# CH32F_V208G-R0.net
KiCad netlist of a schematic drawn in Altium Designer
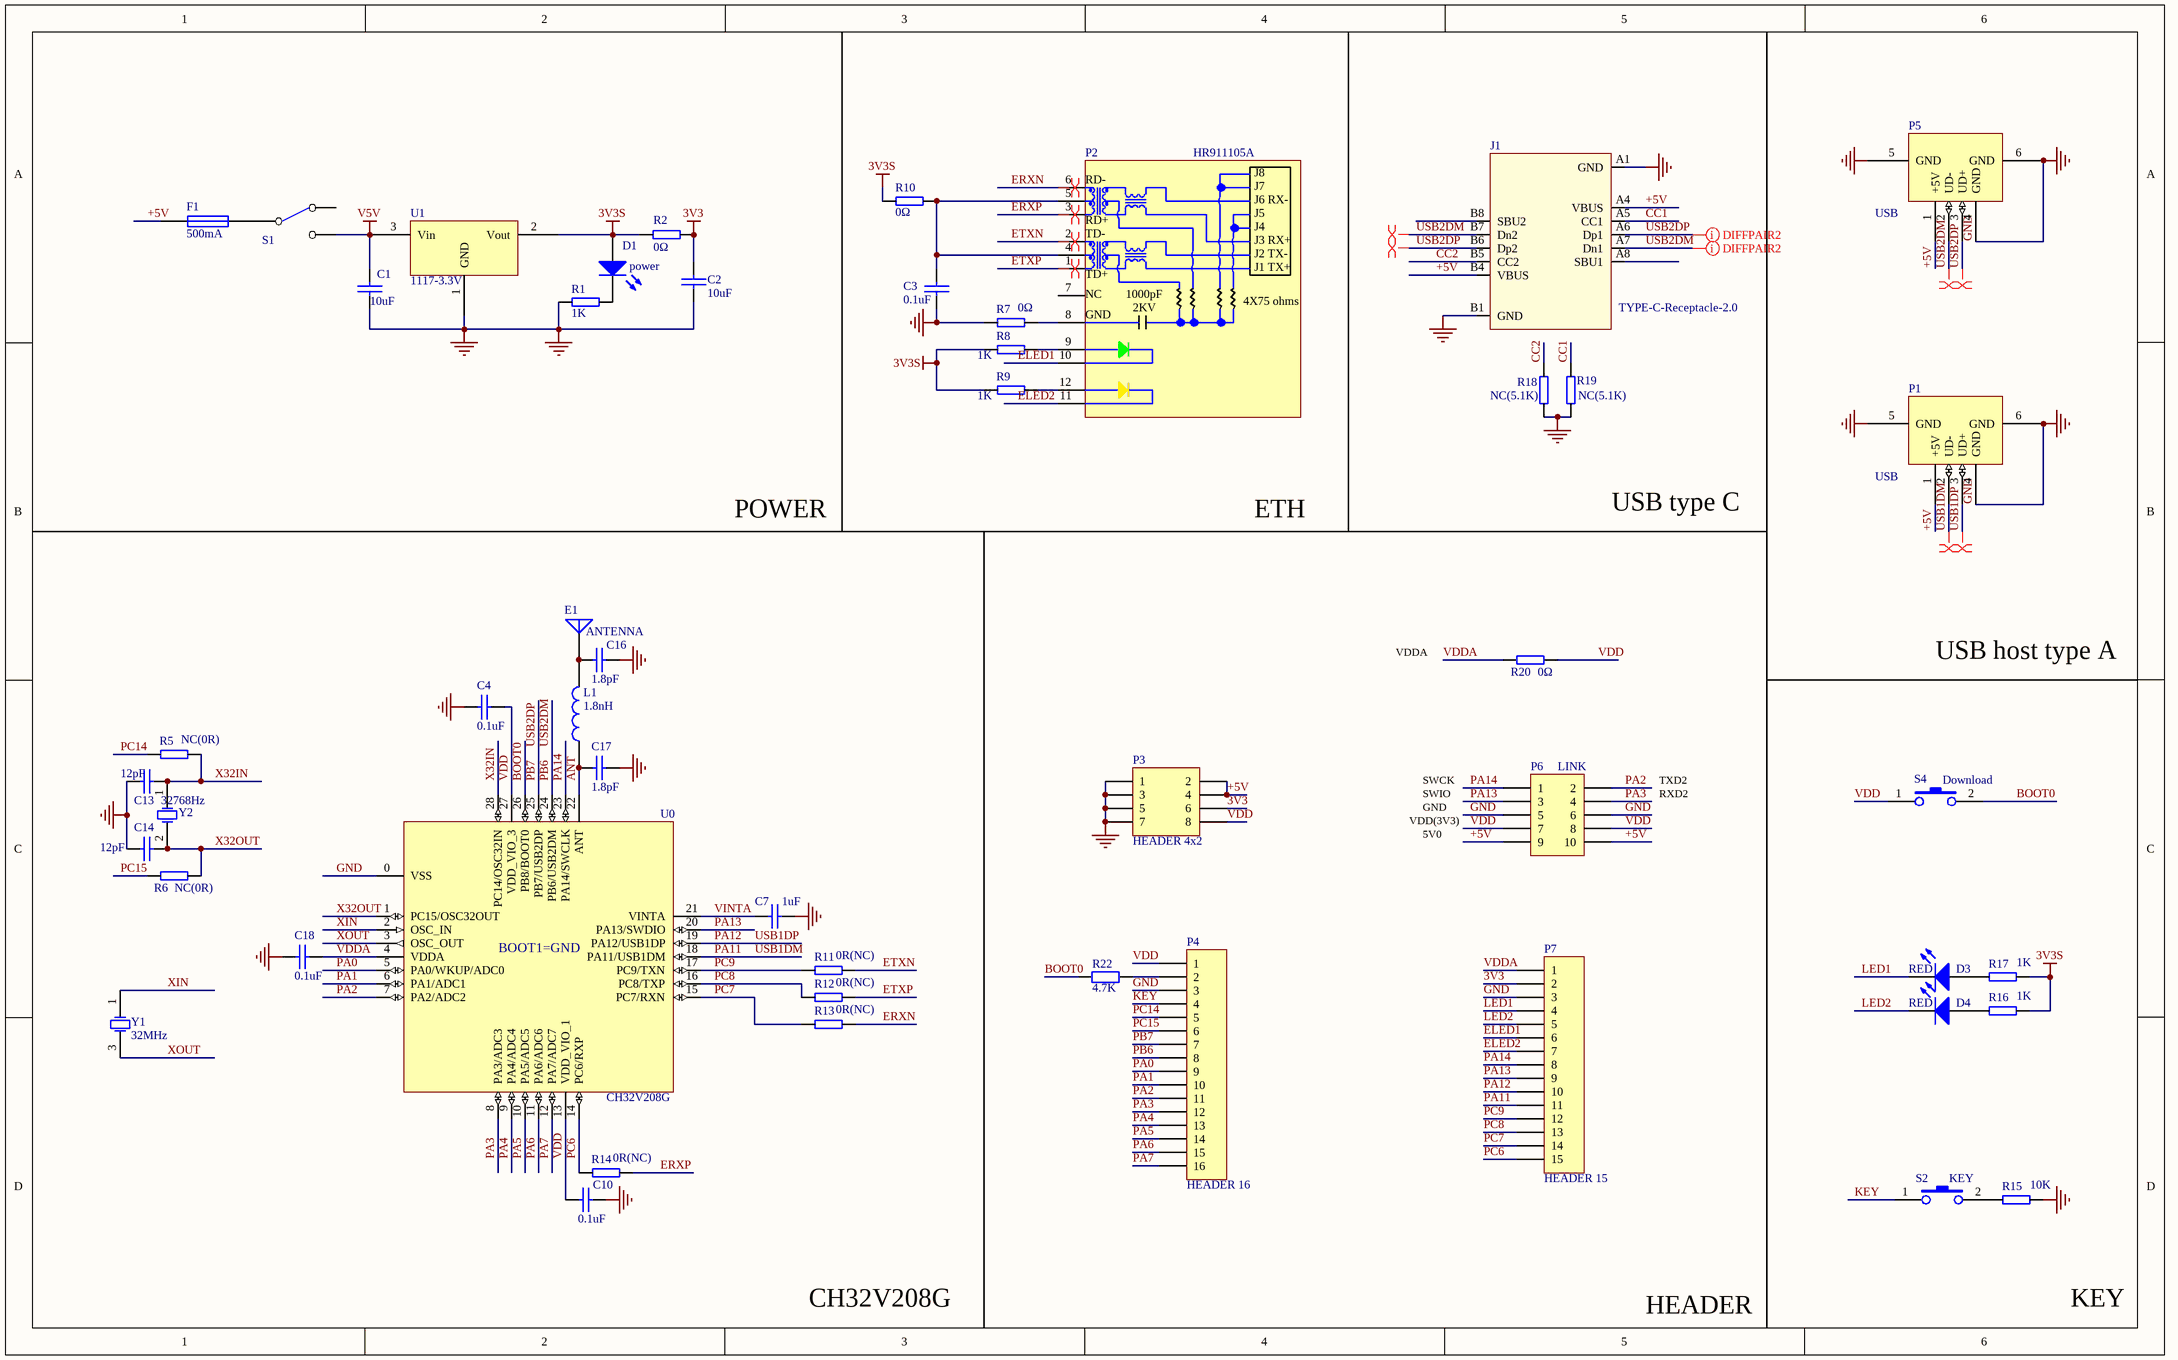
[diagram p0: CH32F&V208G-R0.SchDoc]

(export (version "E")
  (design (tool "Eeschema 10.0.6"))
  (components
    (comp (ref "C1")
      (value "10uF")
      (footprint "3216_C")
      (description "Capacitor")
      (libsource (lib "*") (part "CAP"))
    )
    (comp (ref "C2")
      (value "10uF")
      (footprint "0603_C")
      (description "Capacitor")
      (libsource (lib "*") (part "CAP"))
    )
    (comp (ref "C3")
      (value "0.1uF")
      (footprint "0603_C")
      (description "Capacitor")
      (libsource (lib "*") (part "CAP"))
    )
    (comp (ref "C4")
      (value "0.1uF")
      (footprint "0603_C")
      (description "Capacitor")
      (libsource (lib "") (part "CAP_1"))
    )
    (comp (ref "C7")
      (value "1uF")
      (footprint "0603_C")
      (description "Capacitor")
      (libsource (lib "") (part "CAP_1"))
    )
    (comp (ref "C10")
      (value "0.1uF")
      (footprint "0603_C")
      (description "Capacitor")
      (libsource (lib "") (part "CAP_1"))
    )
    (comp (ref "C13")
      (value "12pF")
      (footprint "0603_C")
      (description "Capacitor")
      (libsource (lib "*") (part "CAP"))
    )
    (comp (ref "C14")
      (value "12pF")
      (footprint "0603_C")
      (description "Capacitor")
      (libsource (lib "*") (part "CAP"))
    )
    (comp (ref "C16")
      (value "1.8pF")
      (footprint "0603_C")
      (description "Capacitor")
      (libsource (lib "") (part "CAP_1"))
    )
    (comp (ref "C17")
      (value "1.8pF")
      (footprint "0603_C")
      (description "Capacitor")
      (libsource (lib "") (part "CAP_1"))
    )
    (comp (ref "C18")
      (value "0.1uF")
      (footprint "0603_C")
      (description "Capacitor")
      (libsource (lib "") (part "CAP_1"))
    )
    (comp (ref "D1")
      (value "power")
      (footprint "0603+")
      (description "Typical INFRARED GaAs LED")
      (fields (field (name "PUBLISHER") "Altium Limited"))
      (libsource (lib "*") (part "LED0"))
    )
    (comp (ref "D3")
      (value "RED")
      (footprint "0603+")
      (description "Typical INFRARED GaAs LED")
      (fields (field (name "PUBLISHER") "Altium Limited"))
      (libsource (lib "*") (part "LED0"))
    )
    (comp (ref "D4")
      (value "RED")
      (footprint "0603+")
      (description "Typical INFRARED GaAs LED")
      (fields (field (name "PUBLISHER") "Altium Limited"))
      (libsource (lib "*") (part "LED0"))
    )
    (comp (ref "E1")
      (value "ANTENNA")
      (footprint "ANT-F-1-2.4G-1.6mmFR4")
      (description "Generic Antenna")
      (libsource (lib "*") (part "ANTENNA"))
    )
    (comp (ref "F1")
      (value "500mA")
      (footprint "0603")
      (description "Fuse")
      (libsource (lib "wch_sch_others") (part "FUSE1"))
    )
    (comp (ref "J1")
      (value "TYPE-C-Receptacle-2.0")
      (footprint "TYPE-C-Receptacle-2.0")
      (description "Type-C USB2.0 母座")
      (libsource (lib "Miscellaneous SCH Lib") (part "TYPE-C-Receptacle-2.0"))
    )
    (comp (ref "L1") (value "1.8nH") (footprint "0603") (libsource (lib "*") (part "INDUCTOR")))
    (comp (ref "P1")
      (value "USB")
      (footprint "USBAF")
      (description "USB Port")
      (libsource (lib "*") (part "USB"))
    )
    (comp (ref "P2") (value "HR911105A") (footprint "HR911105A") (libsource (lib "*") (part "HR911105A")))
    (comp (ref "P3")
      (value "HEADER 4x2")
      (footprint "MYPCB:IDC8-2.54mm")
      (description "Header, 4-Pin, Dual row")
      (libsource (lib "wch_sch_others") (part "HEADER 4x2"))
    )
    (comp (ref "P4")
      (value "HEADER 16")
      (footprint "SIP16-2.54mm")
      (description "Header, 16-Pin")
      (libsource (lib "wch_sch_others") (part "HEADER 16"))
    )
    (comp (ref "P5")
      (value "USB")
      (footprint "USBAF")
      (description "USB Port")
      (libsource (lib "*") (part "USB"))
    )
    (comp (ref "P6")
      (value "LINK")
      (footprint "IDC10-2.54mm")
      (description "Header, 5-Pin, Dual row, Right Angle")
      (fields (field (name "PUBLISHER") "Altium Limited"))
      (libsource (lib "Miscellaneous Connectors") (part "Header 5X2H"))
    )
    (comp (ref "P7")
      (value "HEADER 15")
      (footprint "SIP15-2.54mm")
      (description "Header, 15-Pin")
      (libsource (lib "wch_sch_others") (part "HEADER 15"))
    )
    (comp (ref "R1") (value "1K") (footprint "0603") (libsource (lib "wch_sch_others") (part "RES")))
    (comp (ref "R2") (value "0Ω") (footprint "0603") (libsource (lib "wch_sch_others") (part "RES")))
    (comp (ref "R5") (value "NC(0R)") (footprint "0603") (libsource (lib "wch_sch_others") (part "RES")))
    (comp (ref "R6") (value "NC(0R)") (footprint "0603") (libsource (lib "wch_sch_others") (part "RES")))
    (comp (ref "R7") (value "0Ω") (footprint "0603") (libsource (lib "wch_sch_others") (part "RES")))
    (comp (ref "R8") (value "1K") (footprint "0603") (libsource (lib "wch_sch_others") (part "RES")))
    (comp (ref "R9") (value "1K") (footprint "0603") (libsource (lib "wch_sch_others") (part "RES")))
    (comp (ref "R10") (value "0Ω") (footprint "0603") (libsource (lib "wch_sch_others") (part "RES")))
    (comp (ref "R11") (value "0R(NC)") (footprint "0603") (libsource (lib "wch_sch_others") (part "RES")))
    (comp (ref "R12") (value "0R(NC)") (footprint "0603") (libsource (lib "wch_sch_others") (part "RES")))
    (comp (ref "R13") (value "0R(NC)") (footprint "0603") (libsource (lib "wch_sch_others") (part "RES")))
    (comp (ref "R14") (value "0R(NC)") (footprint "0603") (libsource (lib "wch_sch_others") (part "RES")))
    (comp (ref "R15") (value "10K") (footprint "0603") (libsource (lib "wch_sch_others") (part "RES")))
    (comp (ref "R16") (value "1K") (footprint "0603") (libsource (lib "wch_sch_others") (part "RES")))
    (comp (ref "R17") (value "1K") (footprint "0603") (libsource (lib "wch_sch_others") (part "RES")))
    (comp (ref "R18") (value "NC(5.1K)") (footprint "0603") (libsource (lib "wch_sch_others") (part "RES")))
    (comp (ref "R19") (value "NC(5.1K)") (footprint "0603") (libsource (lib "wch_sch_others") (part "RES")))
    (comp (ref "R20") (value "0Ω") (footprint "0603") (libsource (lib "*") (part "R")))
    (comp (ref "R22")
      (value "4.7K")
      (footprint "0603")
      (description "Resistor")
      (libsource (lib "Miscellaneous Devices") (part "Res2"))
    )
    (comp (ref "S1") (value "SW SPDT") (footprint "SW1") (libsource (lib "*") (part "SW SPDT")))
    (comp (ref "S2")
      (value "KEY")
      (footprint "SMD_6.1x3.65x2.5mm-KEY")
      (libsource (lib "wch_sch_others") (part "KEY1"))
    )
    (comp (ref "S4")
      (value "Download")
      (footprint "SMD_6.1x3.65x2.5mm-KEY")
      (libsource (lib "wch_sch_others") (part "KEY1"))
    )
    (comp (ref "U0")
      (value "CH32V208G")
      (footprint "QFN28_4x4")
      (description "RISC-V BLE5.3 MCU, 10M Ethernet, 2*USB, CAN")
      (libsource (lib "CHXXX") (part "CH32V208G"))
    )
    (comp (ref "U1")
      (value "1117-3.3V")
      (footprint "SOT-223")
      (libsource (lib "wch_sch_others") (part "1117-3.3V"))
    )
    (comp (ref "Y1")
      (value "32MHz")
      (footprint "XT3225")
      (description "Crystal Oscillator")
      (fields (field (name "PUBLISHER") "Altium Limited"))
      (libsource (lib "*") (part "XTAL"))
    )
    (comp (ref "Y2")
      (value "32768Hz")
      (footprint "FC-135")
      (description "Crystal Oscillator")
      (fields (field (name "PUBLISHER") "Altium Limited"))
      (libsource (lib "") (part "XTAL_1"))
    )
  )
  (nets
    (net (code "1") (name "/+5V") (class "Default")
      (node (ref "F1") (pin "1") (pinfunction "1_1") (pintype "passive"))
      (node (ref "J1") (pin "A4") (pinfunction "VBUS_A4") (pintype "passive"))
      (node (ref "J1") (pin "B4") (pinfunction "VBUS_B4") (pintype "passive"))
      (node (ref "P1") (pin "1") (pinfunction "+5V_1") (pintype "power_in"))
      (node (ref "P3") (pin "2") (pinfunction "2_2") (pintype "passive"))
      (node (ref "P3") (pin "4") (pinfunction "4_4") (pintype "passive"))
      (node (ref "P5") (pin "1") (pinfunction "+5V_1") (pintype "power_in"))
      (node (ref "P6") (pin "10") (pinfunction "10_10") (pintype "passive"))
      (node (ref "P6") (pin "9") (pinfunction "9_9") (pintype "passive"))
    )
    (net (code "2") (name "/ANT") (class "Default")
      (node (ref "C17") (pin "2") (pinfunction "2_2") (pintype "passive"))
      (node (ref "L1") (pin "1") (pinfunction "1_1") (pintype "passive"))
      (node (ref "U0") (pin "22") (pinfunction "ANT_22") (pintype "power_in"))
    )
    (net (code "3") (name "/BOOT0") (class "Default")
      (node (ref "R22") (pin "1") (pinfunction "1_1") (pintype "passive"))
      (node (ref "S4") (pin "2") (pinfunction "2_2") (pintype "passive"))
      (node (ref "U0") (pin "26") (pinfunction "PB8/BOOT0_26") (pintype "bidirectional"))
    )
    (net (code "4") (name "/CC1") (class "Default")
      (node (ref "J1") (pin "A5") (pinfunction "CC1_A5") (pintype "passive"))
      (node (ref "R19") (pin "1") (pintype "passive"))
    )
    (net (code "5") (name "/CC2") (class "Default")
      (node (ref "J1") (pin "B5") (pinfunction "CC2_B5") (pintype "passive"))
      (node (ref "R18") (pin "1") (pintype "passive"))
    )
    (net (code "6") (name "/ELED1") (class "Default")
      (node (ref "P2") (pin "10") (pintype "passive"))
      (node (ref "P7") (pin "6") (pinfunction "6_6") (pintype "passive"))
    )
    (net (code "7") (name "/ELED2") (class "Default")
      (node (ref "P2") (pin "11") (pintype "passive"))
      (node (ref "P7") (pin "7") (pinfunction "7_7") (pintype "passive"))
    )
    (net (code "8") (name "/ERXN") (class "Default")
      (node (ref "P2") (pin "6") (pintype "passive"))
      (node (ref "R13") (pin "2") (pintype "passive"))
    )
    (net (code "9") (name "/ERXP") (class "Default")
      (node (ref "P2") (pin "3") (pintype "passive"))
      (node (ref "R14") (pin "2") (pintype "passive"))
    )
    (net (code "10") (name "/ETXN") (class "Default")
      (node (ref "P2") (pin "2") (pintype "passive"))
      (node (ref "R11") (pin "2") (pintype "passive"))
    )
    (net (code "11") (name "/ETXP") (class "Default")
      (node (ref "P2") (pin "1") (pintype "passive"))
      (node (ref "R12") (pin "2") (pintype "passive"))
    )
    (net (code "12") (name "/KEY") (class "Default")
      (node (ref "P4") (pin "4") (pinfunction "4_4") (pintype "passive"))
      (node (ref "S2") (pin "1") (pinfunction "1_1") (pintype "passive"))
    )
    (net (code "13") (name "/LED1") (class "Default")
      (node (ref "D3") (pin "2") (pinfunction "K_2") (pintype "passive"))
      (node (ref "P7") (pin "4") (pinfunction "4_4") (pintype "passive"))
    )
    (net (code "14") (name "/LED2") (class "Default")
      (node (ref "D4") (pin "2") (pinfunction "K_2") (pintype "passive"))
      (node (ref "P7") (pin "5") (pinfunction "5_5") (pintype "passive"))
    )
    (net (code "15") (name "/PA0") (class "Default")
      (node (ref "P4") (pin "9") (pinfunction "9_9") (pintype "passive"))
      (node (ref "U0") (pin "5") (pinfunction "PA0/WKUP/ADC0_5") (pintype "bidirectional"))
    )
    (net (code "16") (name "/PA1") (class "Default")
      (node (ref "P4") (pin "10") (pinfunction "10_10") (pintype "passive"))
      (node (ref "U0") (pin "6") (pinfunction "PA1/ADC1_6") (pintype "bidirectional"))
    )
    (net (code "17") (name "/PA2") (class "Default")
      (node (ref "P4") (pin "11") (pinfunction "11_11") (pintype "passive"))
      (node (ref "P6") (pin "2") (pinfunction "2_2") (pintype "passive"))
      (node (ref "U0") (pin "7") (pinfunction "PA2/ADC2_7") (pintype "bidirectional"))
    )
    (net (code "18") (name "/PA3") (class "Default")
      (node (ref "P4") (pin "12") (pinfunction "12_12") (pintype "passive"))
      (node (ref "P6") (pin "4") (pinfunction "4_4") (pintype "passive"))
      (node (ref "U0") (pin "8") (pinfunction "PA3/ADC3_8") (pintype "bidirectional"))
    )
    (net (code "19") (name "/PA4") (class "Default")
      (node (ref "P4") (pin "13") (pinfunction "13_13") (pintype "passive"))
      (node (ref "U0") (pin "9") (pinfunction "PA4/ADC4_9") (pintype "bidirectional"))
    )
    (net (code "20") (name "/PA5") (class "Default")
      (node (ref "P4") (pin "14") (pinfunction "14_14") (pintype "passive"))
      (node (ref "U0") (pin "10") (pinfunction "PA5/ADC5_10") (pintype "bidirectional"))
    )
    (net (code "21") (name "/PA6") (class "Default")
      (node (ref "P4") (pin "15") (pinfunction "15_15") (pintype "passive"))
      (node (ref "U0") (pin "11") (pinfunction "PA6/ADC6_11") (pintype "bidirectional"))
    )
    (net (code "22") (name "/PA7") (class "Default")
      (node (ref "P4") (pin "16") (pinfunction "16_16") (pintype "passive"))
      (node (ref "U0") (pin "12") (pinfunction "PA7/ADC7_12") (pintype "bidirectional"))
    )
    (net (code "23") (name "/PA11") (class "Default")
      (node (ref "P1") (pin "2") (pinfunction "UD-_2") (pintype "bidirectional"))
      (node (ref "P7") (pin "11") (pinfunction "11_11") (pintype "passive"))
      (node (ref "U0") (pin "18") (pinfunction "PA11/USB1DM_18") (pintype "bidirectional"))
    )
    (net (code "24") (name "/PA12") (class "Default")
      (node (ref "P1") (pin "3") (pinfunction "UD+_3") (pintype "bidirectional"))
      (node (ref "P7") (pin "10") (pinfunction "10_10") (pintype "passive"))
      (node (ref "U0") (pin "19") (pinfunction "PA12/USB1DP_19") (pintype "bidirectional"))
    )
    (net (code "25") (name "/PA13") (class "Default")
      (node (ref "P6") (pin "3") (pinfunction "3_3") (pintype "passive"))
      (node (ref "P7") (pin "9") (pinfunction "9_9") (pintype "passive"))
      (node (ref "U0") (pin "20") (pinfunction "PA13/SWDIO_20") (pintype "bidirectional"))
    )
    (net (code "26") (name "/PA14") (class "Default")
      (node (ref "P6") (pin "1") (pinfunction "1_1") (pintype "passive"))
      (node (ref "P7") (pin "8") (pinfunction "8_8") (pintype "passive"))
      (node (ref "U0") (pin "23") (pinfunction "PA14/SWCLK_23") (pintype "bidirectional"))
    )
    (net (code "27") (name "/PB6") (class "Default")
      (node (ref "J1") (pin "A7") (pinfunction "Dn1_A7") (pintype "passive"))
      (node (ref "J1") (pin "B7") (pinfunction "Dn2_B7") (pintype "passive"))
      (node (ref "P4") (pin "8") (pinfunction "8_8") (pintype "passive"))
      (node (ref "P5") (pin "2") (pinfunction "UD-_2") (pintype "bidirectional"))
      (node (ref "U0") (pin "24") (pinfunction "PB6/USB2DM_24") (pintype "bidirectional"))
    )
    (net (code "28") (name "/PB7") (class "Default")
      (node (ref "J1") (pin "A6") (pinfunction "Dp1_A6") (pintype "passive"))
      (node (ref "J1") (pin "B6") (pinfunction "Dp2_B6") (pintype "passive"))
      (node (ref "P4") (pin "7") (pinfunction "7_7") (pintype "passive"))
      (node (ref "P5") (pin "3") (pinfunction "UD+_3") (pintype "bidirectional"))
      (node (ref "U0") (pin "25") (pinfunction "PB7/USB2DP_25") (pintype "bidirectional"))
    )
    (net (code "29") (name "/PC6") (class "Default")
      (node (ref "P7") (pin "15") (pinfunction "15_15") (pintype "passive"))
      (node (ref "R14") (pin "1") (pintype "passive"))
      (node (ref "U0") (pin "14") (pinfunction "PC6/RXP_14") (pintype "bidirectional"))
    )
    (net (code "30") (name "/PC7") (class "Default")
      (node (ref "P7") (pin "14") (pinfunction "14_14") (pintype "passive"))
      (node (ref "R13") (pin "1") (pintype "passive"))
      (node (ref "U0") (pin "15") (pinfunction "PC7/RXN_15") (pintype "bidirectional"))
    )
    (net (code "31") (name "/PC8") (class "Default")
      (node (ref "P7") (pin "13") (pinfunction "13_13") (pintype "passive"))
      (node (ref "R12") (pin "1") (pintype "passive"))
      (node (ref "U0") (pin "16") (pinfunction "PC8/TXP_16") (pintype "bidirectional"))
    )
    (net (code "32") (name "/PC9") (class "Default")
      (node (ref "P7") (pin "12") (pinfunction "12_12") (pintype "passive"))
      (node (ref "R11") (pin "1") (pintype "passive"))
      (node (ref "U0") (pin "17") (pinfunction "PC9/TXN_17") (pintype "bidirectional"))
    )
    (net (code "33") (name "/PC14") (class "Default")
      (node (ref "P4") (pin "5") (pinfunction "5_5") (pintype "passive"))
      (node (ref "R5") (pin "1") (pintype "passive"))
    )
    (net (code "34") (name "/PC15") (class "Default")
      (node (ref "P4") (pin "6") (pinfunction "6_6") (pintype "passive"))
      (node (ref "R6") (pin "1") (pintype "passive"))
    )
    (net (code "35") (name "/VDD") (class "Default")
      (node (ref "C10") (pin "2") (pinfunction "2_2") (pintype "passive"))
      (node (ref "C4") (pin "1") (pinfunction "1_1") (pintype "passive"))
      (node (ref "P3") (pin "8") (pinfunction "8_8") (pintype "passive"))
      (node (ref "P4") (pin "1") (pinfunction "1_1") (pintype "passive"))
      (node (ref "P6") (pin "7") (pinfunction "7_7") (pintype "passive"))
      (node (ref "P6") (pin "8") (pinfunction "8_8") (pintype "passive"))
      (node (ref "R20") (pin "1") (pinfunction "1_1") (pintype "passive"))
      (node (ref "S4") (pin "1") (pinfunction "1_1") (pintype "passive"))
      (node (ref "U0") (pin "13") (pinfunction "VDD_VIO_1_13") (pintype "power_in"))
      (node (ref "U0") (pin "27") (pinfunction "VDD_VIO_3_27") (pintype "power_in"))
    )
    (net (code "36") (name "/VDDA") (class "Default")
      (node (ref "C18") (pin "1") (pinfunction "1_1") (pintype "passive"))
      (node (ref "P7") (pin "1") (pinfunction "1_1") (pintype "passive"))
      (node (ref "R20") (pin "2") (pinfunction "2_2") (pintype "passive"))
      (node (ref "U0") (pin "4") (pinfunction "VDDA_4") (pintype "power_in"))
    )
    (net (code "37") (name "/VINTA") (class "Default")
      (node (ref "C7") (pin "1") (pinfunction "1_1") (pintype "passive"))
      (node (ref "U0") (pin "21") (pinfunction "VINTA_21") (pintype "power_in"))
    )
    (net (code "38") (name "/X32IN") (class "Default")
      (node (ref "C13") (pin "2") (pinfunction "2_2") (pintype "passive"))
      (node (ref "R5") (pin "2") (pintype "passive"))
      (node (ref "U0") (pin "28") (pinfunction "PC14/OSC32IN_28") (pintype "bidirectional"))
      (node (ref "Y2") (pin "1") (pinfunction "OSC1_1") (pintype "passive"))
    )
    (net (code "39") (name "/X32OUT") (class "Default")
      (node (ref "C14") (pin "2") (pinfunction "2_2") (pintype "passive"))
      (node (ref "R6") (pin "2") (pintype "passive"))
      (node (ref "U0") (pin "1") (pinfunction "PC15/OSC32OUT_1") (pintype "bidirectional"))
      (node (ref "Y2") (pin "2") (pinfunction "OSC2_2") (pintype "passive"))
    )
    (net (code "40") (name "/XIN") (class "Default")
      (node (ref "U0") (pin "2") (pinfunction "OSC_IN_2") (pintype "input"))
      (node (ref "Y1") (pin "1") (pinfunction "OSC1_1") (pintype "passive"))
    )
    (net (code "41") (name "/XOUT") (class "Default")
      (node (ref "U0") (pin "3") (pinfunction "OSC_OUT_3") (pintype "output"))
      (node (ref "Y1") (pin "3") (pinfunction "OSC2_3") (pintype "passive"))
    )
    (net (code "42") (name "3V3") (class "Default")
      (node (ref "C2") (pin "1") (pinfunction "1_1") (pintype "passive"))
      (node (ref "P3") (pin "6") (pinfunction "6_6") (pintype "passive"))
      (node (ref "P7") (pin "2") (pinfunction "2_2") (pintype "passive"))
      (node (ref "R2") (pin "1") (pintype "passive"))
    )
    (net (code "43") (name "3V3S") (class "Default")
      (node (ref "D1") (pin "1") (pinfunction "A_1") (pintype "passive"))
      (node (ref "R10") (pin "2") (pintype "passive"))
      (node (ref "R16") (pin "1") (pintype "passive"))
      (node (ref "R17") (pin "1") (pintype "passive"))
      (node (ref "R2") (pin "2") (pintype "passive"))
      (node (ref "R8") (pin "1") (pintype "passive"))
      (node (ref "R9") (pin "1") (pintype "passive"))
      (node (ref "U1") (pin "2") (pinfunction "Vout_2") (pintype "passive"))
    )
    (net (code "44") (name "GND") (class "Default")
      (node (ref "C1") (pin "2") (pinfunction "2_2") (pintype "passive"))
      (node (ref "C10") (pin "1") (pinfunction "1_1") (pintype "passive"))
      (node (ref "C13") (pin "1") (pinfunction "1_1") (pintype "passive"))
      (node (ref "C14") (pin "1") (pinfunction "1_1") (pintype "passive"))
      (node (ref "C16") (pin "1") (pinfunction "1_1") (pintype "passive"))
      (node (ref "C17") (pin "1") (pinfunction "1_1") (pintype "passive"))
      (node (ref "C18") (pin "2") (pinfunction "2_2") (pintype "passive"))
      (node (ref "C2") (pin "2") (pinfunction "2_2") (pintype "passive"))
      (node (ref "C3") (pin "1") (pinfunction "1_1") (pintype "passive"))
      (node (ref "C4") (pin "2") (pinfunction "2_2") (pintype "passive"))
      (node (ref "C7") (pin "2") (pinfunction "2_2") (pintype "passive"))
      (node (ref "J1") (pin "A1") (pinfunction "GND_A1") (pintype "passive"))
      (node (ref "J1") (pin "B1") (pinfunction "GND_B1") (pintype "passive"))
      (node (ref "P1") (pin "4") (pinfunction "GND_4") (pintype "power_in"))
      (node (ref "P1") (pin "5") (pinfunction "GND_5") (pintype "power_in"))
      (node (ref "P1") (pin "6") (pinfunction "GND_6") (pintype "power_in"))
      (node (ref "P3") (pin "1") (pinfunction "1_1") (pintype "passive"))
      (node (ref "P3") (pin "3") (pinfunction "3_3") (pintype "passive"))
      (node (ref "P3") (pin "5") (pinfunction "5_5") (pintype "passive"))
      (node (ref "P3") (pin "7") (pinfunction "7_7") (pintype "passive"))
      (node (ref "P4") (pin "3") (pinfunction "3_3") (pintype "passive"))
      (node (ref "P5") (pin "4") (pinfunction "GND_4") (pintype "power_in"))
      (node (ref "P5") (pin "5") (pinfunction "GND_5") (pintype "power_in"))
      (node (ref "P5") (pin "6") (pinfunction "GND_6") (pintype "power_in"))
      (node (ref "P6") (pin "5") (pinfunction "5_5") (pintype "passive"))
      (node (ref "P6") (pin "6") (pinfunction "6_6") (pintype "passive"))
      (node (ref "P7") (pin "3") (pinfunction "3_3") (pintype "passive"))
      (node (ref "R1") (pin "1") (pintype "passive"))
      (node (ref "R15") (pin "1") (pintype "passive"))
      (node (ref "R18") (pin "2") (pintype "passive"))
      (node (ref "R19") (pin "2") (pintype "passive"))
      (node (ref "R7") (pin "1") (pintype "passive"))
      (node (ref "U0") (pin "0") (pinfunction "VSS_0") (pintype "power_in"))
      (node (ref "U1") (pin "1") (pinfunction "GND_1") (pintype "passive"))
    )
    (net (code "45") (name "Net-(C3-Pad2)") (class "Default")
      (node (ref "C3") (pin "2") (pinfunction "2_2") (pintype "passive"))
      (node (ref "P2") (pin "4") (pintype "passive"))
      (node (ref "P2") (pin "5") (pintype "passive"))
      (node (ref "R10") (pin "1") (pintype "passive"))
    )
    (net (code "46") (name "Net-(D1-K)") (class "Default")
      (node (ref "D1") (pin "2") (pinfunction "K_2") (pintype "passive"))
      (node (ref "R1") (pin "2") (pintype "passive"))
    )
    (net (code "47") (name "Net-(D3-A)") (class "Default")
      (node (ref "D3") (pin "1") (pinfunction "A_1") (pintype "passive"))
      (node (ref "R17") (pin "2") (pintype "passive"))
    )
    (net (code "48") (name "Net-(D4-A)") (class "Default")
      (node (ref "D4") (pin "1") (pinfunction "A_1") (pintype "passive"))
      (node (ref "R16") (pin "2") (pintype "passive"))
    )
    (net (code "49") (name "Net-(E1-A)") (class "Default")
      (node (ref "C16") (pin "2") (pinfunction "2_2") (pintype "passive"))
      (node (ref "E1") (pin "1") (pinfunction "A_1") (pintype "passive"))
      (node (ref "L1") (pin "2") (pinfunction "2_2") (pintype "passive"))
    )
    (net (code "50") (name "Net-(P2-Pad8)") (class "Default")
      (node (ref "P2") (pin "8") (pintype "passive"))
      (node (ref "R7") (pin "2") (pintype "passive"))
    )
    (net (code "51") (name "Net-(P2-Pad9)") (class "Default")
      (node (ref "P2") (pin "9") (pintype "passive"))
      (node (ref "R8") (pin "2") (pintype "passive"))
    )
    (net (code "52") (name "Net-(P2-Pad12)") (class "Default")
      (node (ref "P2") (pin "12") (pintype "passive"))
      (node (ref "R9") (pin "2") (pintype "passive"))
    )
    (net (code "53") (name "Net-(P4-Pad2)") (class "Default")
      (node (ref "P4") (pin "2") (pinfunction "2_2") (pintype "passive"))
      (node (ref "R22") (pin "2") (pinfunction "2_2") (pintype "passive"))
    )
    (net (code "54") (name "Net-(R15-Pad2)") (class "Default")
      (node (ref "R15") (pin "2") (pintype "passive"))
      (node (ref "S2") (pin "2") (pinfunction "2_2") (pintype "passive"))
    )
    (net (code "55") (name "Net-(S1-COMMON)") (class "Default")
      (node (ref "F1") (pin "2") (pinfunction "2_2") (pintype "passive"))
      (node (ref "S1") (pin "1") (pinfunction "COMMON_1") (pintype "passive"))
    )
    (net (code "56") (name "V5V") (class "Default")
      (node (ref "C1") (pin "1") (pinfunction "1_1") (pintype "passive"))
      (node (ref "S1") (pin "2") (pinfunction "NC_2") (pintype "passive"))
      (node (ref "U1") (pin "3") (pinfunction "Vin_3") (pintype "passive"))
    )
    (net (code "57") (name "unconnected-(J1-SBU1-PadA8)") (class "Default")
      (node (ref "J1") (pin "A8") (pinfunction "SBU1_A8") (pintype "passive"))
    )
    (net (code "58") (name "unconnected-(J1-SBU2-PadB8)") (class "Default")
      (node (ref "J1") (pin "B8") (pinfunction "SBU2_B8") (pintype "passive"))
    )
    (net (code "59") (name "unconnected-(P2-Pad7)") (class "Default")
      (node (ref "P2") (pin "7") (pintype "passive"))
    )
    (net (code "60") (name "unconnected-(S1-NO-Pad3)") (class "Default")
      (node (ref "S1") (pin "3") (pinfunction "NO_3") (pintype "passive"))
    )
  )
)
